# controller2.net
KiCad netlist of a schematic drawn in EAGLE
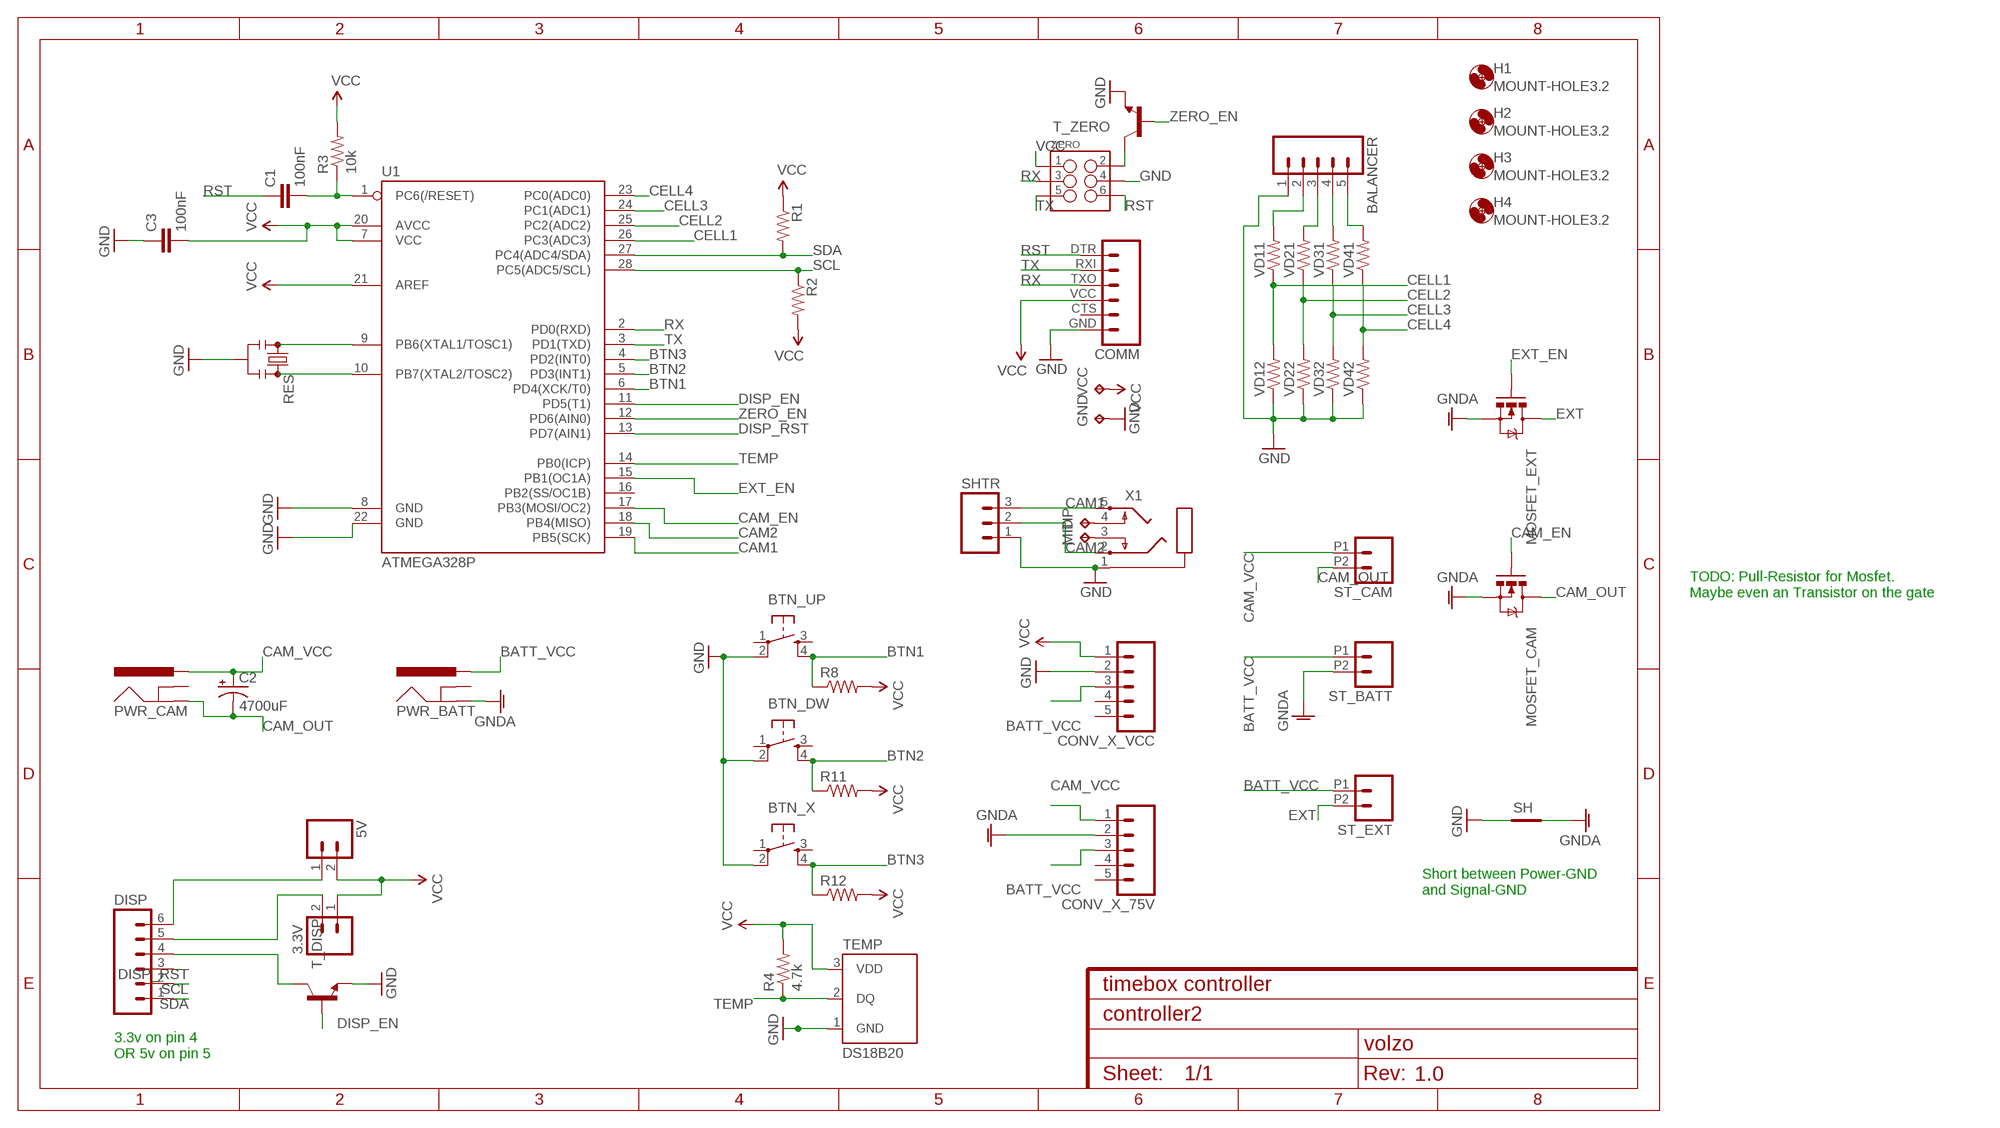
[diagram p0: schematic, sheet 1]

(export (version "E")
  (design (tool "Eeschema 10.0.6"))
  (components
    (comp (ref "3.3V")
      (value "M02LOCK")
      (footprint "eagle-import:1X02_LOCK")
      (libsource (lib "eagle-import") (part "M02LOCK"))
    )
    (comp (ref "5V")
      (value "M02LOCK")
      (footprint "eagle-import:1X02_LOCK")
      (libsource (lib "eagle-import") (part "M02LOCK"))
    )
    (comp (ref "BALANCER")
      (value "M05LOCK")
      (footprint "eagle-import:1X05_LOCK")
      (libsource (lib "eagle-import") (part "M05LOCK"))
    )
    (comp (ref "BTN_DW")
      (value "TAC_SWITCHPTH")
      (footprint "eagle-import:TACTILE-PTH")
      (libsource (lib "eagle-import") (part "TAC_SWITCHPTH"))
    )
    (comp (ref "BTN_UP")
      (value "TAC_SWITCHPTH")
      (footprint "eagle-import:TACTILE-PTH")
      (libsource (lib "eagle-import") (part "TAC_SWITCHPTH"))
    )
    (comp (ref "BTN_X")
      (value "TAC_SWITCHPTH")
      (footprint "eagle-import:TACTILE-PTH")
      (libsource (lib "eagle-import") (part "TAC_SWITCHPTH"))
    )
    (comp (ref "C1")
      (value "100nF")
      (footprint "eagle-import:CAP-PTH-SMALL")
      (libsource (lib "eagle-import") (part "CAPPTH"))
    )
    (comp (ref "C2")
      (value "4700uF")
      (footprint "eagle-import:CPOL-RADIAL-1000UF-63V")
      (libsource (lib "eagle-import") (part "CAP_POLPTH3"))
    )
    (comp (ref "C3")
      (value "100nF")
      (footprint "eagle-import:CAP-PTH-SMALL")
      (libsource (lib "eagle-import") (part "CAPPTH"))
    )
    (comp (ref "COMM")
      (value "FTDI_BASICPTH")
      (footprint "eagle-import:FTDI_BASIC")
      (libsource (lib "eagle-import") (part "FTDI_BASICPTH"))
    )
    (comp (ref "CONV_X_75V")
      (value "M05LOCK")
      (footprint "eagle-import:1X05_LOCK")
      (libsource (lib "eagle-import") (part "M05LOCK"))
    )
    (comp (ref "CONV_X_VCC")
      (value "M05LOCK")
      (footprint "eagle-import:1X05_LOCK")
      (libsource (lib "eagle-import") (part "M05LOCK"))
    )
    (comp (ref "DISP")
      (value "M06FEMALE_LOCK")
      (footprint "eagle-import:1X06_FEMALE_LOCK.010")
      (libsource (lib "eagle-import") (part "M06FEMALE_LOCK"))
    )
    (comp (ref "GND")
      (value "TPTP14SQ")
      (footprint "eagle-import:TP14SQ")
      (libsource (lib "eagle-import") (part "TPTP14SQ"))
    )
    (comp (ref "H1")
      (value "MOUNT-HOLE3.2")
      (footprint "eagle-import:3,2")
      (libsource (lib "eagle-import") (part "MOUNT-HOLE3.2"))
    )
    (comp (ref "H2")
      (value "MOUNT-HOLE3.2")
      (footprint "eagle-import:3,2")
      (libsource (lib "eagle-import") (part "MOUNT-HOLE3.2"))
    )
    (comp (ref "H3")
      (value "MOUNT-HOLE3.2")
      (footprint "eagle-import:3,2")
      (libsource (lib "eagle-import") (part "MOUNT-HOLE3.2"))
    )
    (comp (ref "H4")
      (value "MOUNT-HOLE3.2")
      (footprint "eagle-import:3,2")
      (libsource (lib "eagle-import") (part "MOUNT-HOLE3.2"))
    )
    (comp (ref "MID")
      (value "TPTP14SQ")
      (footprint "eagle-import:TP14SQ")
      (libsource (lib "eagle-import") (part "TPTP14SQ"))
    )
    (comp (ref "MOSFET_CAM")
      (value "MOSFET-NCHANNELFQP30N06L")
      (footprint "eagle-import:TO220V")
      (libsource (lib "eagle-import") (part "MOSFET-NCHANNELFQP30N06L"))
    )
    (comp (ref "MOSFET_EXT")
      (value "MOSFET-NCHANNELFQP30N06L")
      (footprint "eagle-import:TO220V")
      (libsource (lib "eagle-import") (part "MOSFET-NCHANNELFQP30N06L"))
    )
    (comp (ref "PWR_BATT")
      (value "POWER_JACKPTH_BREAD")
      (footprint "eagle-import:POWER_JACK_PTH_BREAD")
      (libsource (lib "eagle-import") (part "POWER_JACKPTH_BREAD"))
    )
    (comp (ref "PWR_CAM")
      (value "POWER_JACKPTH_BREAD")
      (footprint "eagle-import:POWER_JACK_PTH_BREAD")
      (libsource (lib "eagle-import") (part "POWER_JACKPTH_BREAD"))
    )
    (comp (ref "R1")
      (value "RESISTORAXIAL-0.3")
      (footprint "eagle-import:AXIAL-0.3")
      (libsource (lib "eagle-import") (part "RESISTORAXIAL-0.3"))
    )
    (comp (ref "R2")
      (value "RESISTORAXIAL-0.3")
      (footprint "eagle-import:AXIAL-0.3")
      (libsource (lib "eagle-import") (part "RESISTORAXIAL-0.3"))
    )
    (comp (ref "R3")
      (value "10k")
      (footprint "eagle-import:AXIAL-0.3")
      (libsource (lib "eagle-import") (part "RESISTORAXIAL-0.3"))
    )
    (comp (ref "R4")
      (value "4.7k")
      (footprint "eagle-import:AXIAL-0.3")
      (libsource (lib "eagle-import") (part "RESISTORAXIAL-0.3"))
    )
    (comp (ref "R8")
      (value "RESISTORAXIAL-0.3")
      (footprint "eagle-import:AXIAL-0.3")
      (libsource (lib "eagle-import") (part "RESISTORAXIAL-0.3"))
    )
    (comp (ref "R11")
      (value "RESISTORAXIAL-0.3")
      (footprint "eagle-import:AXIAL-0.3")
      (libsource (lib "eagle-import") (part "RESISTORAXIAL-0.3"))
    )
    (comp (ref "R12")
      (value "RESISTORAXIAL-0.3")
      (footprint "eagle-import:AXIAL-0.3")
      (libsource (lib "eagle-import") (part "RESISTORAXIAL-0.3"))
    )
    (comp (ref "RES")
      (value "RESONATORPTH")
      (footprint "eagle-import:RESONATOR-PTH")
      (libsource (lib "eagle-import") (part "RESONATORPTH"))
    )
    (comp (ref "SH")
      (value "SHORT-HT5")
      (footprint "eagle-import:SHORT_TOP-50")
      (libsource (lib "eagle-import") (part "SHORT-HT5"))
    )
    (comp (ref "SHTR")
      (value "M03LOCK")
      (footprint "eagle-import:1X03_LOCK")
      (libsource (lib "eagle-import") (part "M03LOCK"))
    )
    (comp (ref "ST_BATT")
      (value "M022.54MM_SCREWTERM")
      (footprint "eagle-import:1X02_2.54_SCREWTERM")
      (libsource (lib "eagle-import") (part "M022.54MM_SCREWTERM"))
    )
    (comp (ref "ST_CAM")
      (value "M022.54MM_SCREWTERM")
      (footprint "eagle-import:1X02_2.54_SCREWTERM")
      (libsource (lib "eagle-import") (part "M022.54MM_SCREWTERM"))
    )
    (comp (ref "ST_EXT")
      (value "M022.54MM_SCREWTERM")
      (footprint "eagle-import:1X02_2.54_SCREWTERM")
      (libsource (lib "eagle-import") (part "M022.54MM_SCREWTERM"))
    )
    (comp (ref "TEMP")
      (value "DS18B20")
      (footprint "eagle-import:TO-92-AMMO")
      (libsource (lib "eagle-import") (part "DS18B20"))
    )
    (comp (ref "TIP")
      (value "TPTP14SQ")
      (footprint "eagle-import:TP14SQ")
      (libsource (lib "eagle-import") (part "TPTP14SQ"))
    )
    (comp (ref "T_DISP")
      (value "TRANSISTOR_NPN2N3904")
      (footprint "eagle-import:TO-92")
      (libsource (lib "eagle-import") (part "TRANSISTOR_NPN2N3904"))
    )
    (comp (ref "T_ZERO")
      (value "TRANSISTOR_NPN2N3904")
      (footprint "eagle-import:TO-92")
      (libsource (lib "eagle-import") (part "TRANSISTOR_NPN2N3904"))
    )
    (comp (ref "U1")
      (value "ATMEGA328P")
      (footprint "eagle-import:DIL28-3")
      (libsource (lib "eagle-import") (part "ATMEGA328P_PDIP"))
    )
    (comp (ref "VCC")
      (value "TPTP14SQ")
      (footprint "eagle-import:TP14SQ")
      (libsource (lib "eagle-import") (part "TPTP14SQ"))
    )
    (comp (ref "VD11")
      (value "RESISTORAXIAL-0.3")
      (footprint "eagle-import:AXIAL-0.3")
      (libsource (lib "eagle-import") (part "RESISTORAXIAL-0.3"))
    )
    (comp (ref "VD12")
      (value "RESISTORAXIAL-0.3")
      (footprint "eagle-import:AXIAL-0.3")
      (libsource (lib "eagle-import") (part "RESISTORAXIAL-0.3"))
    )
    (comp (ref "VD21")
      (value "RESISTORAXIAL-0.3")
      (footprint "eagle-import:AXIAL-0.3")
      (libsource (lib "eagle-import") (part "RESISTORAXIAL-0.3"))
    )
    (comp (ref "VD22")
      (value "RESISTORAXIAL-0.3")
      (footprint "eagle-import:AXIAL-0.3")
      (libsource (lib "eagle-import") (part "RESISTORAXIAL-0.3"))
    )
    (comp (ref "VD31")
      (value "RESISTORAXIAL-0.3")
      (footprint "eagle-import:AXIAL-0.3")
      (libsource (lib "eagle-import") (part "RESISTORAXIAL-0.3"))
    )
    (comp (ref "VD32")
      (value "RESISTORAXIAL-0.3")
      (footprint "eagle-import:AXIAL-0.3")
      (libsource (lib "eagle-import") (part "RESISTORAXIAL-0.3"))
    )
    (comp (ref "VD41")
      (value "RESISTORAXIAL-0.3")
      (footprint "eagle-import:AXIAL-0.3")
      (libsource (lib "eagle-import") (part "RESISTORAXIAL-0.3"))
    )
    (comp (ref "VD42")
      (value "RESISTORAXIAL-0.3")
      (footprint "eagle-import:AXIAL-0.3")
      (libsource (lib "eagle-import") (part "RESISTORAXIAL-0.3"))
    )
    (comp (ref "X1")
      (value "STEREOJACK")
      (footprint "eagle-import:STX3100")
      (libsource (lib "eagle-import") (part "STEREOJACK"))
    )
    (comp (ref "ZERO")
      (value "M03X2SHROUD")
      (footprint "eagle-import:2X3-SHROUDED")
      (libsource (lib "eagle-import") (part "M03X2SHROUD"))
    )
  )
  (nets
    (net (code "1") (name "/BATT_VCC") (class "Default")
      (node (ref "CONV_X_75V") (pin "3") (pinfunction "3_3") (pintype "passive"))
      (node (ref "CONV_X_VCC") (pin "3") (pinfunction "3_3") (pintype "passive"))
      (node (ref "PWR_BATT") (pin "PWR") (pinfunction "PWR_PWR") (pintype "bidirectional"))
      (node (ref "ST_BATT") (pin "P1") (pinfunction "1_P1") (pintype "passive"))
      (node (ref "ST_EXT") (pin "P1") (pinfunction "1_P1") (pintype "passive"))
    )
    (net (code "2") (name "/BTN1") (class "Default")
      (node (ref "BTN_UP") (pin "4") (pinfunction "4_4") (pintype "passive"))
      (node (ref "R8") (pin "P$1") (pinfunction "1_P$1") (pintype "passive"))
      (node (ref "U1") (pin "6") (pinfunction "PD4(XCK/T0)_6") (pintype "bidirectional"))
    )
    (net (code "3") (name "/BTN2") (class "Default")
      (node (ref "BTN_DW") (pin "4") (pinfunction "4_4") (pintype "passive"))
      (node (ref "R11") (pin "P$1") (pinfunction "1_P$1") (pintype "passive"))
      (node (ref "U1") (pin "5") (pinfunction "PD3(INT1)_5") (pintype "bidirectional"))
    )
    (net (code "4") (name "/BTN3") (class "Default")
      (node (ref "BTN_X") (pin "4") (pinfunction "4_4") (pintype "passive"))
      (node (ref "R12") (pin "P$1") (pinfunction "1_P$1") (pintype "passive"))
      (node (ref "U1") (pin "4") (pinfunction "PD2(INT0)_4") (pintype "bidirectional"))
    )
    (net (code "5") (name "/CAM1") (class "Default")
      (node (ref "SHTR") (pin "3") (pinfunction "3_3") (pintype "passive"))
      (node (ref "U1") (pin "19") (pinfunction "PB5(SCK)_19") (pintype "bidirectional"))
      (node (ref "X1") (pin "5") (pinfunction "5_5") (pintype "passive"))
    )
    (net (code "6") (name "/CAM2") (class "Default")
      (node (ref "SHTR") (pin "2") (pinfunction "2_2") (pintype "passive"))
      (node (ref "U1") (pin "18") (pinfunction "PB4(MISO)_18") (pintype "bidirectional"))
      (node (ref "X1") (pin "2") (pinfunction "2_2") (pintype "passive"))
    )
    (net (code "7") (name "/CAM_EN") (class "Default")
      (node (ref "MOSFET_CAM") (pin "1") (pinfunction "G_1") (pintype "passive"))
      (node (ref "U1") (pin "17") (pinfunction "PB3(MOSI/OC2)_17") (pintype "bidirectional"))
    )
    (net (code "8") (name "/CAM_OUT") (class "Default")
      (node (ref "C2") (pin "2") (pinfunction "-_2") (pintype "passive"))
      (node (ref "MOSFET_CAM") (pin "2") (pinfunction "D_2") (pintype "passive"))
      (node (ref "PWR_CAM") (pin "GND") (pinfunction "GND_GND") (pintype "bidirectional"))
      (node (ref "ST_CAM") (pin "P2") (pinfunction "2_P2") (pintype "passive"))
    )
    (net (code "9") (name "/CAM_VCC") (class "Default")
      (node (ref "C2") (pin "1") (pinfunction "+_1") (pintype "passive"))
      (node (ref "CONV_X_75V") (pin "1") (pinfunction "1_1") (pintype "passive"))
      (node (ref "PWR_CAM") (pin "PWR") (pinfunction "PWR_PWR") (pintype "bidirectional"))
      (node (ref "ST_CAM") (pin "P1") (pinfunction "1_P1") (pintype "passive"))
    )
    (net (code "10") (name "/CELL1") (class "Default")
      (node (ref "U1") (pin "26") (pinfunction "PC3(ADC3)_26") (pintype "bidirectional"))
      (node (ref "VD11") (pin "P$1") (pinfunction "1_P$1") (pintype "passive"))
      (node (ref "VD12") (pin "P$2") (pinfunction "2_P$2") (pintype "passive"))
    )
    (net (code "11") (name "/CELL2") (class "Default")
      (node (ref "U1") (pin "25") (pinfunction "PC2(ADC2)_25") (pintype "bidirectional"))
      (node (ref "VD21") (pin "P$1") (pinfunction "1_P$1") (pintype "passive"))
      (node (ref "VD22") (pin "P$2") (pinfunction "2_P$2") (pintype "passive"))
    )
    (net (code "12") (name "/CELL3") (class "Default")
      (node (ref "U1") (pin "24") (pinfunction "PC1(ADC1)_24") (pintype "bidirectional"))
      (node (ref "VD31") (pin "P$1") (pinfunction "1_P$1") (pintype "passive"))
      (node (ref "VD32") (pin "P$2") (pinfunction "2_P$2") (pintype "passive"))
    )
    (net (code "13") (name "/CELL4") (class "Default")
      (node (ref "U1") (pin "23") (pinfunction "PC0(ADC0)_23") (pintype "bidirectional"))
      (node (ref "VD41") (pin "P$1") (pinfunction "1_P$1") (pintype "passive"))
      (node (ref "VD42") (pin "P$2") (pinfunction "2_P$2") (pintype "passive"))
    )
    (net (code "14") (name "/DISP_EN") (class "Default")
      (node (ref "T_DISP") (pin "2") (pinfunction "B_2") (pintype "passive"))
      (node (ref "U1") (pin "11") (pinfunction "PD5(T1)_11") (pintype "bidirectional"))
    )
    (net (code "15") (name "/DISP_RST") (class "Default")
      (node (ref "DISP") (pin "3") (pinfunction "3_3") (pintype "passive"))
      (node (ref "U1") (pin "13") (pinfunction "PD7(AIN1)_13") (pintype "bidirectional"))
    )
    (net (code "16") (name "/EXT") (class "Default")
      (node (ref "MOSFET_EXT") (pin "2") (pinfunction "D_2") (pintype "passive"))
      (node (ref "ST_EXT") (pin "P2") (pinfunction "2_P2") (pintype "passive"))
    )
    (net (code "17") (name "/EXT_EN") (class "Default")
      (node (ref "MOSFET_EXT") (pin "1") (pinfunction "G_1") (pintype "passive"))
      (node (ref "U1") (pin "15") (pinfunction "PB1(OC1A)_15") (pintype "bidirectional"))
    )
    (net (code "18") (name "/RST") (class "Default")
      (node (ref "C1") (pin "1") (pinfunction "1_1") (pintype "passive"))
      (node (ref "COMM") (pin "DTR") (pinfunction "1_DTR") (pintype "passive"))
      (node (ref "ZERO") (pin "6") (pinfunction "6_6") (pintype "bidirectional"))
    )
    (net (code "19") (name "/RX") (class "Default")
      (node (ref "COMM") (pin "TXO") (pinfunction "3_TXO") (pintype "passive"))
      (node (ref "U1") (pin "2") (pinfunction "PD0(RXD)_2") (pintype "bidirectional"))
      (node (ref "ZERO") (pin "3") (pinfunction "3_3") (pintype "bidirectional"))
    )
    (net (code "20") (name "/SCL") (class "Default")
      (node (ref "DISP") (pin "2") (pinfunction "2_2") (pintype "passive"))
      (node (ref "R2") (pin "P$1") (pinfunction "1_P$1") (pintype "passive"))
      (node (ref "U1") (pin "28") (pinfunction "PC5(ADC5/SCL)_28") (pintype "bidirectional"))
    )
    (net (code "21") (name "/SDA") (class "Default")
      (node (ref "DISP") (pin "1") (pinfunction "1_1") (pintype "passive"))
      (node (ref "R1") (pin "P$2") (pinfunction "2_P$2") (pintype "passive"))
      (node (ref "U1") (pin "27") (pinfunction "PC4(ADC4/SDA)_27") (pintype "bidirectional"))
    )
    (net (code "22") (name "/TEMP") (class "Default")
      (node (ref "R4") (pin "P$1") (pinfunction "1_P$1") (pintype "passive"))
      (node (ref "TEMP") (pin "2") (pinfunction "DQ_2") (pintype "bidirectional"))
      (node (ref "U1") (pin "14") (pinfunction "PB0(ICP)_14") (pintype "bidirectional"))
    )
    (net (code "23") (name "/TX") (class "Default")
      (node (ref "COMM") (pin "RXI") (pinfunction "2_RXI") (pintype "passive"))
      (node (ref "U1") (pin "3") (pinfunction "PD1(TXD)_3") (pintype "bidirectional"))
      (node (ref "ZERO") (pin "5") (pinfunction "5_5") (pintype "bidirectional"))
    )
    (net (code "24") (name "/ZERO_EN") (class "Default")
      (node (ref "T_ZERO") (pin "2") (pinfunction "B_2") (pintype "passive"))
      (node (ref "U1") (pin "12") (pinfunction "PD6(AIN0)_12") (pintype "bidirectional"))
    )
    (net (code "25") (name "GND") (class "Default")
      (node (ref "BALANCER") (pin "1") (pinfunction "1_1") (pintype "passive"))
      (node (ref "BTN_DW") (pin "2") (pinfunction "2_2") (pintype "passive"))
      (node (ref "BTN_UP") (pin "2") (pinfunction "2_2") (pintype "passive"))
      (node (ref "BTN_X") (pin "2") (pinfunction "2_2") (pintype "passive"))
      (node (ref "C3") (pin "1") (pinfunction "1_1") (pintype "passive"))
      (node (ref "COMM") (pin "GND") (pinfunction "6_GND") (pintype "passive"))
      (node (ref "CONV_X_VCC") (pin "2") (pinfunction "2_2") (pintype "passive"))
      (node (ref "GND") (pin "TP") (pinfunction "TP_TP") (pintype "input"))
      (node (ref "RES") (pin "2") (pinfunction "2_2") (pintype "passive"))
      (node (ref "SH") (pin "1") (pinfunction "P$1_1") (pintype "bidirectional"))
      (node (ref "SHTR") (pin "1") (pinfunction "1_1") (pintype "passive"))
      (node (ref "TEMP") (pin "1") (pinfunction "GND_1") (pintype "power_in"))
      (node (ref "T_DISP") (pin "1") (pinfunction "E_1") (pintype "passive"))
      (node (ref "T_ZERO") (pin "1") (pinfunction "E_1") (pintype "passive"))
      (node (ref "U1") (pin "22") (pinfunction "GND_22") (pintype "bidirectional"))
      (node (ref "U1") (pin "8") (pinfunction "GND_8") (pintype "bidirectional"))
      (node (ref "VD12") (pin "P$1") (pinfunction "1_P$1") (pintype "passive"))
      (node (ref "VD22") (pin "P$1") (pinfunction "1_P$1") (pintype "passive"))
      (node (ref "VD32") (pin "P$1") (pinfunction "1_P$1") (pintype "passive"))
      (node (ref "VD42") (pin "P$1") (pinfunction "1_P$1") (pintype "passive"))
      (node (ref "X1") (pin "1") (pinfunction "1_1") (pintype "passive"))
      (node (ref "ZERO") (pin "4") (pinfunction "4_4") (pintype "bidirectional"))
    )
    (net (code "26") (name "GNDA") (class "Default")
      (node (ref "CONV_X_75V") (pin "2") (pinfunction "2_2") (pintype "passive"))
      (node (ref "MOSFET_CAM") (pin "3") (pinfunction "S_3") (pintype "passive"))
      (node (ref "MOSFET_EXT") (pin "3") (pinfunction "S_3") (pintype "passive"))
      (node (ref "PWR_BATT") (pin "GND") (pinfunction "GND_GND") (pintype "bidirectional"))
      (node (ref "SH") (pin "2") (pinfunction "P$2_2") (pintype "bidirectional"))
      (node (ref "ST_BATT") (pin "P2") (pinfunction "2_P2") (pintype "passive"))
    )
    (net (code "27") (name "Net-(3.3V-Pad2)") (class "Default")
      (node (ref "3.3V") (pin "2") (pinfunction "2_2") (pintype "passive"))
      (node (ref "DISP") (pin "5") (pinfunction "5_5") (pintype "passive"))
    )
    (net (code "28") (name "Net-(5V-Pad1)") (class "Default")
      (node (ref "5V") (pin "1") (pinfunction "1_1") (pintype "passive"))
      (node (ref "DISP") (pin "6") (pinfunction "6_6") (pintype "passive"))
    )
    (net (code "29") (name "Net-(MID-PadTP)") (class "Default")
      (node (ref "MID") (pin "TP") (pinfunction "TP_TP") (pintype "input"))
      (node (ref "X1") (pin "3") (pinfunction "3_3") (pintype "passive"))
    )
    (net (code "30") (name "Net-(R3-1)") (class "Default")
      (node (ref "C1") (pin "2") (pinfunction "2_2") (pintype "passive"))
      (node (ref "R3") (pin "P$1") (pinfunction "1_P$1") (pintype "passive"))
      (node (ref "U1") (pin "1") (pinfunction "PC6(/RESET)_1") (pintype "bidirectional"))
    )
    (net (code "31") (name "Net-(TIP-PadTP)") (class "Default")
      (node (ref "TIP") (pin "TP") (pinfunction "TP_TP") (pintype "input"))
      (node (ref "X1") (pin "4") (pinfunction "4_4") (pintype "passive"))
    )
    (net (code "32") (name "Net-(T_DISP-C)") (class "Default")
      (node (ref "DISP") (pin "4") (pinfunction "4_4") (pintype "passive"))
      (node (ref "T_DISP") (pin "3") (pinfunction "C_3") (pintype "passive"))
    )
    (net (code "33") (name "Net-(T_ZERO-C)") (class "Default")
      (node (ref "T_ZERO") (pin "3") (pinfunction "C_3") (pintype "passive"))
      (node (ref "ZERO") (pin "2") (pinfunction "2_2") (pintype "bidirectional"))
    )
    (net (code "34") (name "Net-(U1-PB6(XTAL1{slash}TOSC1))") (class "Default")
      (node (ref "RES") (pin "1") (pinfunction "1_1") (pintype "passive"))
      (node (ref "U1") (pin "9") (pinfunction "PB6(XTAL1/TOSC1)_9") (pintype "bidirectional"))
    )
    (net (code "35") (name "Net-(U1-PB7(XTAL2{slash}TOSC2))") (class "Default")
      (node (ref "RES") (pin "3") (pinfunction "3_3") (pintype "passive"))
      (node (ref "U1") (pin "10") (pinfunction "PB7(XTAL2/TOSC2)_10") (pintype "bidirectional"))
    )
    (net (code "36") (name "Net-(VD11-2)") (class "Default")
      (node (ref "BALANCER") (pin "2") (pinfunction "2_2") (pintype "passive"))
      (node (ref "VD11") (pin "P$2") (pinfunction "2_P$2") (pintype "passive"))
    )
    (net (code "37") (name "Net-(VD21-2)") (class "Default")
      (node (ref "BALANCER") (pin "3") (pinfunction "3_3") (pintype "passive"))
      (node (ref "VD21") (pin "P$2") (pinfunction "2_P$2") (pintype "passive"))
    )
    (net (code "38") (name "Net-(VD31-2)") (class "Default")
      (node (ref "BALANCER") (pin "4") (pinfunction "4_4") (pintype "passive"))
      (node (ref "VD31") (pin "P$2") (pinfunction "2_P$2") (pintype "passive"))
    )
    (net (code "39") (name "Net-(VD41-2)") (class "Default")
      (node (ref "BALANCER") (pin "5") (pinfunction "5_5") (pintype "passive"))
      (node (ref "VD41") (pin "P$2") (pinfunction "2_P$2") (pintype "passive"))
    )
    (net (code "40") (name "VCC") (class "Default")
      (node (ref "3.3V") (pin "1") (pinfunction "1_1") (pintype "passive"))
      (node (ref "5V") (pin "2") (pinfunction "2_2") (pintype "passive"))
      (node (ref "C3") (pin "2") (pinfunction "2_2") (pintype "passive"))
      (node (ref "COMM") (pin "VCC") (pinfunction "4_VCC") (pintype "passive"))
      (node (ref "CONV_X_VCC") (pin "1") (pinfunction "1_1") (pintype "passive"))
      (node (ref "R1") (pin "P$1") (pinfunction "1_P$1") (pintype "passive"))
      (node (ref "R11") (pin "P$2") (pinfunction "2_P$2") (pintype "passive"))
      (node (ref "R12") (pin "P$2") (pinfunction "2_P$2") (pintype "passive"))
      (node (ref "R2") (pin "P$2") (pinfunction "2_P$2") (pintype "passive"))
      (node (ref "R3") (pin "P$2") (pinfunction "2_P$2") (pintype "passive"))
      (node (ref "R4") (pin "P$2") (pinfunction "2_P$2") (pintype "passive"))
      (node (ref "R8") (pin "P$2") (pinfunction "2_P$2") (pintype "passive"))
      (node (ref "TEMP") (pin "3") (pinfunction "VDD_3") (pintype "power_in"))
      (node (ref "U1") (pin "20") (pinfunction "AVCC_20") (pintype "bidirectional"))
      (node (ref "U1") (pin "21") (pinfunction "AREF_21") (pintype "bidirectional"))
      (node (ref "U1") (pin "7") (pinfunction "VCC_7") (pintype "bidirectional"))
      (node (ref "VCC") (pin "TP") (pinfunction "TP_TP") (pintype "input"))
      (node (ref "ZERO") (pin "1") (pinfunction "1_1") (pintype "bidirectional"))
    )
    (net (code "41") (name "unconnected-(BTN_DW-Pad1)") (class "Default")
      (node (ref "BTN_DW") (pin "1") (pinfunction "1_1") (pintype "passive"))
    )
    (net (code "42") (name "unconnected-(BTN_DW-Pad3)") (class "Default")
      (node (ref "BTN_DW") (pin "3") (pinfunction "3_3") (pintype "passive"))
    )
    (net (code "43") (name "unconnected-(BTN_UP-Pad1)") (class "Default")
      (node (ref "BTN_UP") (pin "1") (pinfunction "1_1") (pintype "passive"))
    )
    (net (code "44") (name "unconnected-(BTN_UP-Pad3)") (class "Default")
      (node (ref "BTN_UP") (pin "3") (pinfunction "3_3") (pintype "passive"))
    )
    (net (code "45") (name "unconnected-(BTN_X-Pad1)") (class "Default")
      (node (ref "BTN_X") (pin "1") (pinfunction "1_1") (pintype "passive"))
    )
    (net (code "46") (name "unconnected-(BTN_X-Pad3)") (class "Default")
      (node (ref "BTN_X") (pin "3") (pinfunction "3_3") (pintype "passive"))
    )
    (net (code "47") (name "unconnected-(COMM-5-PadCTS)") (class "Default")
      (node (ref "COMM") (pin "CTS") (pinfunction "5_CTS") (pintype "passive"))
    )
    (net (code "48") (name "unconnected-(CONV_X_75V-Pad4)") (class "Default")
      (node (ref "CONV_X_75V") (pin "4") (pinfunction "4_4") (pintype "passive"))
    )
    (net (code "49") (name "unconnected-(CONV_X_75V-Pad5)") (class "Default")
      (node (ref "CONV_X_75V") (pin "5") (pinfunction "5_5") (pintype "passive"))
    )
    (net (code "50") (name "unconnected-(CONV_X_VCC-Pad4)") (class "Default")
      (node (ref "CONV_X_VCC") (pin "4") (pinfunction "4_4") (pintype "passive"))
    )
    (net (code "51") (name "unconnected-(CONV_X_VCC-Pad5)") (class "Default")
      (node (ref "CONV_X_VCC") (pin "5") (pinfunction "5_5") (pintype "passive"))
    )
    (net (code "52") (name "unconnected-(PWR_BATT-PadGNDBREAK)") (class "Default")
      (node (ref "PWR_BATT") (pin "GNDBREAK") (pinfunction "GNDBREAK_GNDBREAK") (pintype "bidirectional"))
    )
    (net (code "53") (name "unconnected-(PWR_CAM-PadGNDBREAK)") (class "Default")
      (node (ref "PWR_CAM") (pin "GNDBREAK") (pinfunction "GNDBREAK_GNDBREAK") (pintype "bidirectional"))
    )
    (net (code "54") (name "unconnected-(U1-PB2(SS{slash}OC1B)-Pad16)") (class "Default")
      (node (ref "U1") (pin "16") (pinfunction "PB2(SS/OC1B)_16") (pintype "bidirectional"))
    )
  )
)
